# Day10F206.net
KiCad netlist of a schematic drawn in Altium Designer
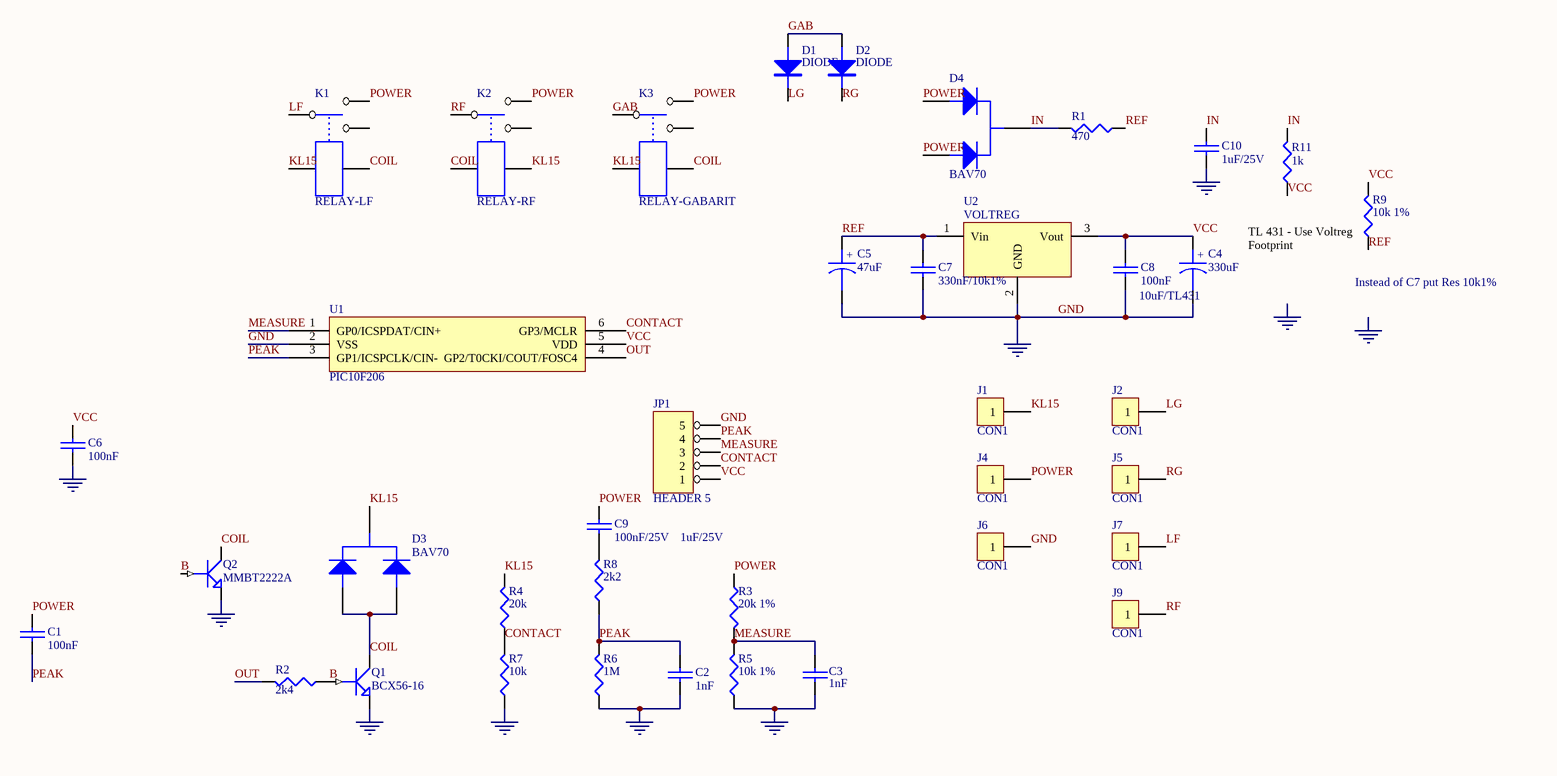
[diagram p0: Day10F206.SchDoc]

(export (version "E")
  (design (tool "Eeschema 10.0.6"))
  (components
    (comp (ref "C1")
      (value "100nF")
      (footprint "0603")
      (description "Capacitor")
      (libsource (lib "*") (part "CAP"))
    )
    (comp (ref "C2")
      (value "1nF")
      (footprint "0603")
      (description "Capacitor")
      (libsource (lib "*") (part "CAP"))
    )
    (comp (ref "C3")
      (value "1nF")
      (footprint "0603")
      (description "Capacitor")
      (libsource (lib "*") (part "CAP"))
    )
    (comp (ref "C4")
      (value "330uF")
      (footprint "RA 5MM")
      (description "Capacitor")
      (libsource (lib "*") (part "CAPACITOR POL"))
    )
    (comp (ref "C5")
      (value "47uF")
      (footprint "RA 5MM")
      (description "Capacitor")
      (libsource (lib "*") (part "CAPACITOR POL"))
    )
    (comp (ref "C6")
      (value "100nF")
      (footprint "0805")
      (description "Capacitor")
      (libsource (lib "*") (part "CAP"))
    )
    (comp (ref "C7")
      (value "330nF/10k1%")
      (footprint "0805")
      (description "Capacitor")
      (libsource (lib "*") (part "CAP"))
    )
    (comp (ref "C8")
      (value "100nF")
      (footprint "0805")
      (description "Capacitor")
      (libsource (lib "*") (part "CAP"))
    )
    (comp (ref "C9")
      (value "100nF/25V")
      (footprint "0603")
      (description "Capacitor")
      (libsource (lib "*") (part "CAP"))
    )
    (comp (ref "C10")
      (value "1uF/25V")
      (footprint "0805")
      (description "Capacitor")
      (libsource (lib "*") (part "CAP"))
    )
    (comp (ref "D1")
      (value "DIODE")
      (footprint "DIODE0.7 - Radial")
      (description "Diode")
      (libsource (lib "Miscellaneous Devices") (part "DIODE"))
    )
    (comp (ref "D2")
      (value "DIODE")
      (footprint "DIODE0.7 - Radial")
      (description "Diode")
      (libsource (lib "Miscellaneous Devices") (part "DIODE"))
    )
    (comp (ref "D3")
      (value "BAV70")
      (footprint "SOT-23")
      (libsource (lib "Devices") (part "DUAL DIODE BAV70"))
    )
    (comp (ref "D4")
      (value "BAV70")
      (footprint "SOT-23")
      (libsource (lib "Devices") (part "DUAL DIODE BAV70"))
    )
    (comp (ref "J1")
      (value "CON1")
      (footprint "SIP1 - WIRE")
      (description "Connector")
      (libsource (lib "Miscellaneous Devices") (part "CON1"))
    )
    (comp (ref "J2")
      (value "CON1")
      (footprint "SIP1 - WIRE")
      (description "Connector")
      (libsource (lib "Miscellaneous Devices") (part "CON1"))
    )
    (comp (ref "J4")
      (value "CON1")
      (footprint "SIP1 - WIRE")
      (description "Connector")
      (libsource (lib "Miscellaneous Devices") (part "CON1"))
    )
    (comp (ref "J5")
      (value "CON1")
      (footprint "SIP1 - WIRE")
      (description "Connector")
      (libsource (lib "Miscellaneous Devices") (part "CON1"))
    )
    (comp (ref "J6")
      (value "CON1")
      (footprint "SIP1 - WIRE")
      (description "Connector")
      (libsource (lib "Miscellaneous Devices") (part "CON1"))
    )
    (comp (ref "J7")
      (value "CON1")
      (footprint "SIP1 - WIRE")
      (description "Connector")
      (libsource (lib "Miscellaneous Devices") (part "CON1"))
    )
    (comp (ref "J9")
      (value "CON1")
      (footprint "SIP1 - WIRE")
      (description "Connector")
      (libsource (lib "Miscellaneous Devices") (part "CON1"))
    )
    (comp (ref "JP1")
      (value "HEADER 5")
      (footprint "SIP5 - PGM 2")
      (libsource (lib "Miscellaneous Devices") (part "HEADER 5"))
    )
    (comp (ref "K1")
      (value "RELAY-LF")
      (footprint "RELAY5PIN")
      (libsource (lib "Miscellaneous Devices") (part "RELAY-SPDT"))
    )
    (comp (ref "K2")
      (value "RELAY-RF")
      (footprint "RELAY5PIN")
      (libsource (lib "Miscellaneous Devices") (part "RELAY-SPDT"))
    )
    (comp (ref "K3")
      (value "RELAY-GABARIT")
      (footprint "RELAY5PIN")
      (libsource (lib "Miscellaneous Devices") (part "RELAY-SPDT"))
    )
    (comp (ref "Q1")
      (value "BCX56-16")
      (footprint "SOT-89")
      (description "NPN Transistor")
      (libsource (lib "Miscellaneous Devices") (part "NPN1"))
    )
    (comp (ref "Q2")
      (value "MMBT2222A")
      (footprint "SOT-23")
      (description "NPN Transistor")
      (libsource (lib "Miscellaneous Devices") (part "NPN1"))
    )
    (comp (ref "R1") (value "470") (footprint "0603") (libsource (lib "Miscellaneous Devices") (part "RES1")))
    (comp (ref "R2") (value "2k4") (footprint "0603") (libsource (lib "Miscellaneous Devices") (part "RES1")))
    (comp (ref "R3")
      (value "20k 1%")
      (footprint "0603")
      (libsource (lib "Miscellaneous Devices") (part "RES1"))
    )
    (comp (ref "R4") (value "20k") (footprint "0805") (libsource (lib "Miscellaneous Devices") (part "RES1")))
    (comp (ref "R5")
      (value "10k 1%")
      (footprint "0603")
      (libsource (lib "Miscellaneous Devices") (part "RES1"))
    )
    (comp (ref "R6") (value "1M") (footprint "0603") (libsource (lib "Miscellaneous Devices") (part "RES1")))
    (comp (ref "R7") (value "10k") (footprint "0603") (libsource (lib "Miscellaneous Devices") (part "RES1")))
    (comp (ref "R8") (value "2k2") (footprint "0603") (libsource (lib "Miscellaneous Devices") (part "RES1")))
    (comp (ref "R9")
      (value "10k 1%")
      (footprint "0805")
      (libsource (lib "Miscellaneous Devices") (part "RES1"))
    )
    (comp (ref "R11") (value "1k") (footprint "0805") (libsource (lib "Miscellaneous Devices") (part "RES1")))
    (comp (ref "U1") (value "PIC10F206") (footprint "SOT23 - 6") (libsource (lib "MCU") (part "PIC10F206")))
    (comp (ref "U2") (value "VOLTREG") (footprint "LINEAR VOLTREG 3") (libsource (lib "*") (part "VOLTREG")))
  )
  (nets
    (net (code "1") (name "/B") (class "Default")
      (node (ref "Q1") (pin "1") (pinfunction "B_1") (pintype "input"))
      (node (ref "Q2") (pin "1") (pinfunction "B_1") (pintype "input"))
      (node (ref "R2") (pin "1") (pinfunction "1_1") (pintype "passive"))
    )
    (net (code "2") (name "/COIL") (class "Default")
      (node (ref "D3") (pin "1") (pinfunction "A1_1") (pintype "passive"))
      (node (ref "D3") (pin "3") (pinfunction "A2_3") (pintype "passive"))
      (node (ref "K1") (pin "5") (pinfunction "5_5") (pintype "passive"))
      (node (ref "K2") (pin "4") (pinfunction "4_4") (pintype "passive"))
      (node (ref "K3") (pin "5") (pinfunction "5_5") (pintype "passive"))
      (node (ref "Q1") (pin "2") (pinfunction "C_2") (pintype "passive"))
      (node (ref "Q2") (pin "2") (pinfunction "C_2") (pintype "passive"))
    )
    (net (code "3") (name "/CONTACT") (class "Default")
      (node (ref "JP1") (pin "2") (pinfunction "2_2") (pintype "passive"))
      (node (ref "R4") (pin "1") (pinfunction "1_1") (pintype "passive"))
      (node (ref "R7") (pin "2") (pinfunction "2_2") (pintype "passive"))
      (node (ref "U1") (pin "6") (pinfunction "GP3/MCLR_6") (pintype "passive"))
    )
    (net (code "4") (name "/GAB") (class "Default")
      (node (ref "D1") (pin "A") (pinfunction "A_A") (pintype "passive"))
      (node (ref "D2") (pin "A") (pinfunction "A_A") (pintype "passive"))
      (node (ref "K3") (pin "1") (pinfunction "1_1") (pintype "passive"))
    )
    (net (code "5") (name "/IN") (class "Default")
      (node (ref "C10") (pin "1") (pinfunction "1_1") (pintype "passive"))
      (node (ref "D4") (pin "2") (pinfunction "K_2") (pintype "passive"))
      (node (ref "R1") (pin "2") (pinfunction "2_2") (pintype "passive"))
      (node (ref "R11") (pin "2") (pinfunction "2_2") (pintype "passive"))
    )
    (net (code "6") (name "/KL15") (class "Default")
      (node (ref "D3") (pin "2") (pinfunction "K_2") (pintype "passive"))
      (node (ref "J1") (pin "1") (pinfunction "1_1") (pintype "passive"))
      (node (ref "K1") (pin "4") (pinfunction "4_4") (pintype "passive"))
      (node (ref "K2") (pin "5") (pinfunction "5_5") (pintype "passive"))
      (node (ref "K3") (pin "4") (pinfunction "4_4") (pintype "passive"))
      (node (ref "R4") (pin "2") (pinfunction "2_2") (pintype "passive"))
    )
    (net (code "7") (name "/LF") (class "Default")
      (node (ref "J7") (pin "1") (pinfunction "1_1") (pintype "passive"))
      (node (ref "K1") (pin "1") (pinfunction "1_1") (pintype "passive"))
    )
    (net (code "8") (name "/LG") (class "Default")
      (node (ref "D1") (pin "K") (pinfunction "K_K") (pintype "passive"))
      (node (ref "J2") (pin "1") (pinfunction "1_1") (pintype "passive"))
    )
    (net (code "9") (name "/MEASURE") (class "Default")
      (node (ref "C3") (pin "2") (pinfunction "2_2") (pintype "passive"))
      (node (ref "JP1") (pin "3") (pinfunction "3_3") (pintype "passive"))
      (node (ref "R3") (pin "2") (pinfunction "2_2") (pintype "passive"))
      (node (ref "R5") (pin "2") (pinfunction "2_2") (pintype "passive"))
      (node (ref "U1") (pin "1") (pinfunction "GP0/ICSPDAT/CIN+_1") (pintype "passive"))
    )
    (net (code "10") (name "/OUT") (class "Default")
      (node (ref "R2") (pin "2") (pinfunction "2_2") (pintype "passive"))
      (node (ref "U1") (pin "4") (pinfunction "GP2/T0CKI/COUT/FOSC4_4") (pintype "passive"))
    )
    (net (code "11") (name "/PEAK") (class "Default")
      (node (ref "C1") (pin "2") (pinfunction "2_2") (pintype "passive"))
      (node (ref "C2") (pin "1") (pinfunction "1_1") (pintype "passive"))
      (node (ref "JP1") (pin "4") (pinfunction "4_4") (pintype "passive"))
      (node (ref "R6") (pin "2") (pinfunction "2_2") (pintype "passive"))
      (node (ref "R8") (pin "1") (pinfunction "1_1") (pintype "passive"))
      (node (ref "U1") (pin "3") (pinfunction "GP1/ICSPCLK/CIN-_3") (pintype "passive"))
    )
    (net (code "12") (name "/POWER") (class "Default")
      (node (ref "C1") (pin "1") (pinfunction "1_1") (pintype "passive"))
      (node (ref "C9") (pin "1") (pinfunction "1_1") (pintype "passive"))
      (node (ref "D4") (pin "1") (pinfunction "A1_1") (pintype "passive"))
      (node (ref "D4") (pin "3") (pinfunction "A2_3") (pintype "passive"))
      (node (ref "J4") (pin "1") (pinfunction "1_1") (pintype "passive"))
      (node (ref "K1") (pin "2") (pinfunction "2_2") (pintype "passive"))
      (node (ref "K2") (pin "2") (pinfunction "2_2") (pintype "passive"))
      (node (ref "K3") (pin "2") (pinfunction "2_2") (pintype "passive"))
      (node (ref "R3") (pin "1") (pinfunction "1_1") (pintype "passive"))
    )
    (net (code "13") (name "/REF") (class "Default")
      (node (ref "C5") (pin "1") (pinfunction "1_1") (pintype "passive"))
      (node (ref "C7") (pin "1") (pinfunction "1_1") (pintype "passive"))
      (node (ref "R1") (pin "1") (pinfunction "1_1") (pintype "passive"))
      (node (ref "R9") (pin "1") (pinfunction "1_1") (pintype "passive"))
      (node (ref "U2") (pin "1") (pinfunction "Vin_1") (pintype "passive"))
    )
    (net (code "14") (name "/RF") (class "Default")
      (node (ref "J9") (pin "1") (pinfunction "1_1") (pintype "passive"))
      (node (ref "K2") (pin "1") (pinfunction "1_1") (pintype "passive"))
    )
    (net (code "15") (name "/RG") (class "Default")
      (node (ref "D2") (pin "K") (pinfunction "K_K") (pintype "passive"))
      (node (ref "J5") (pin "1") (pinfunction "1_1") (pintype "passive"))
    )
    (net (code "16") (name "/VCC") (class "Default")
      (node (ref "C4") (pin "1") (pinfunction "1_1") (pintype "passive"))
      (node (ref "C6") (pin "1") (pinfunction "1_1") (pintype "passive"))
      (node (ref "C8") (pin "1") (pinfunction "1_1") (pintype "passive"))
      (node (ref "JP1") (pin "1") (pinfunction "1_1") (pintype "passive"))
      (node (ref "R11") (pin "1") (pinfunction "1_1") (pintype "passive"))
      (node (ref "R9") (pin "2") (pinfunction "2_2") (pintype "passive"))
      (node (ref "U1") (pin "5") (pinfunction "VDD_5") (pintype "passive"))
      (node (ref "U2") (pin "3") (pinfunction "Vout_3") (pintype "passive"))
    )
    (net (code "17") (name "GND") (class "Default")
      (node (ref "C10") (pin "2") (pinfunction "2_2") (pintype "passive"))
      (node (ref "C2") (pin "2") (pinfunction "2_2") (pintype "passive"))
      (node (ref "C3") (pin "1") (pinfunction "1_1") (pintype "passive"))
      (node (ref "C4") (pin "2") (pinfunction "2_2") (pintype "passive"))
      (node (ref "C5") (pin "2") (pinfunction "2_2") (pintype "passive"))
      (node (ref "C6") (pin "2") (pinfunction "2_2") (pintype "passive"))
      (node (ref "C7") (pin "2") (pinfunction "2_2") (pintype "passive"))
      (node (ref "C8") (pin "2") (pinfunction "2_2") (pintype "passive"))
      (node (ref "J6") (pin "1") (pinfunction "1_1") (pintype "passive"))
      (node (ref "JP1") (pin "5") (pinfunction "5_5") (pintype "passive"))
      (node (ref "Q1") (pin "3") (pinfunction "E_3") (pintype "passive"))
      (node (ref "Q2") (pin "3") (pinfunction "E_3") (pintype "passive"))
      (node (ref "R5") (pin "1") (pinfunction "1_1") (pintype "passive"))
      (node (ref "R6") (pin "1") (pinfunction "1_1") (pintype "passive"))
      (node (ref "R7") (pin "1") (pinfunction "1_1") (pintype "passive"))
      (node (ref "U1") (pin "2") (pinfunction "VSS_2") (pintype "passive"))
      (node (ref "U2") (pin "2") (pinfunction "GND_2") (pintype "passive"))
    )
    (net (code "18") (name "Net-(C9-Pad2)") (class "Default")
      (node (ref "C9") (pin "2") (pinfunction "2_2") (pintype "passive"))
      (node (ref "R8") (pin "2") (pinfunction "2_2") (pintype "passive"))
    )
    (net (code "19") (name "unconnected-(K1-Pad3)") (class "Default")
      (node (ref "K1") (pin "3") (pinfunction "3_3") (pintype "passive"))
    )
    (net (code "20") (name "unconnected-(K2-Pad3)") (class "Default")
      (node (ref "K2") (pin "3") (pinfunction "3_3") (pintype "passive"))
    )
    (net (code "21") (name "unconnected-(K3-Pad3)") (class "Default")
      (node (ref "K3") (pin "3") (pinfunction "3_3") (pintype "passive"))
    )
  )
)
